# display2.net
KiCad netlist of a schematic drawn in EAGLE
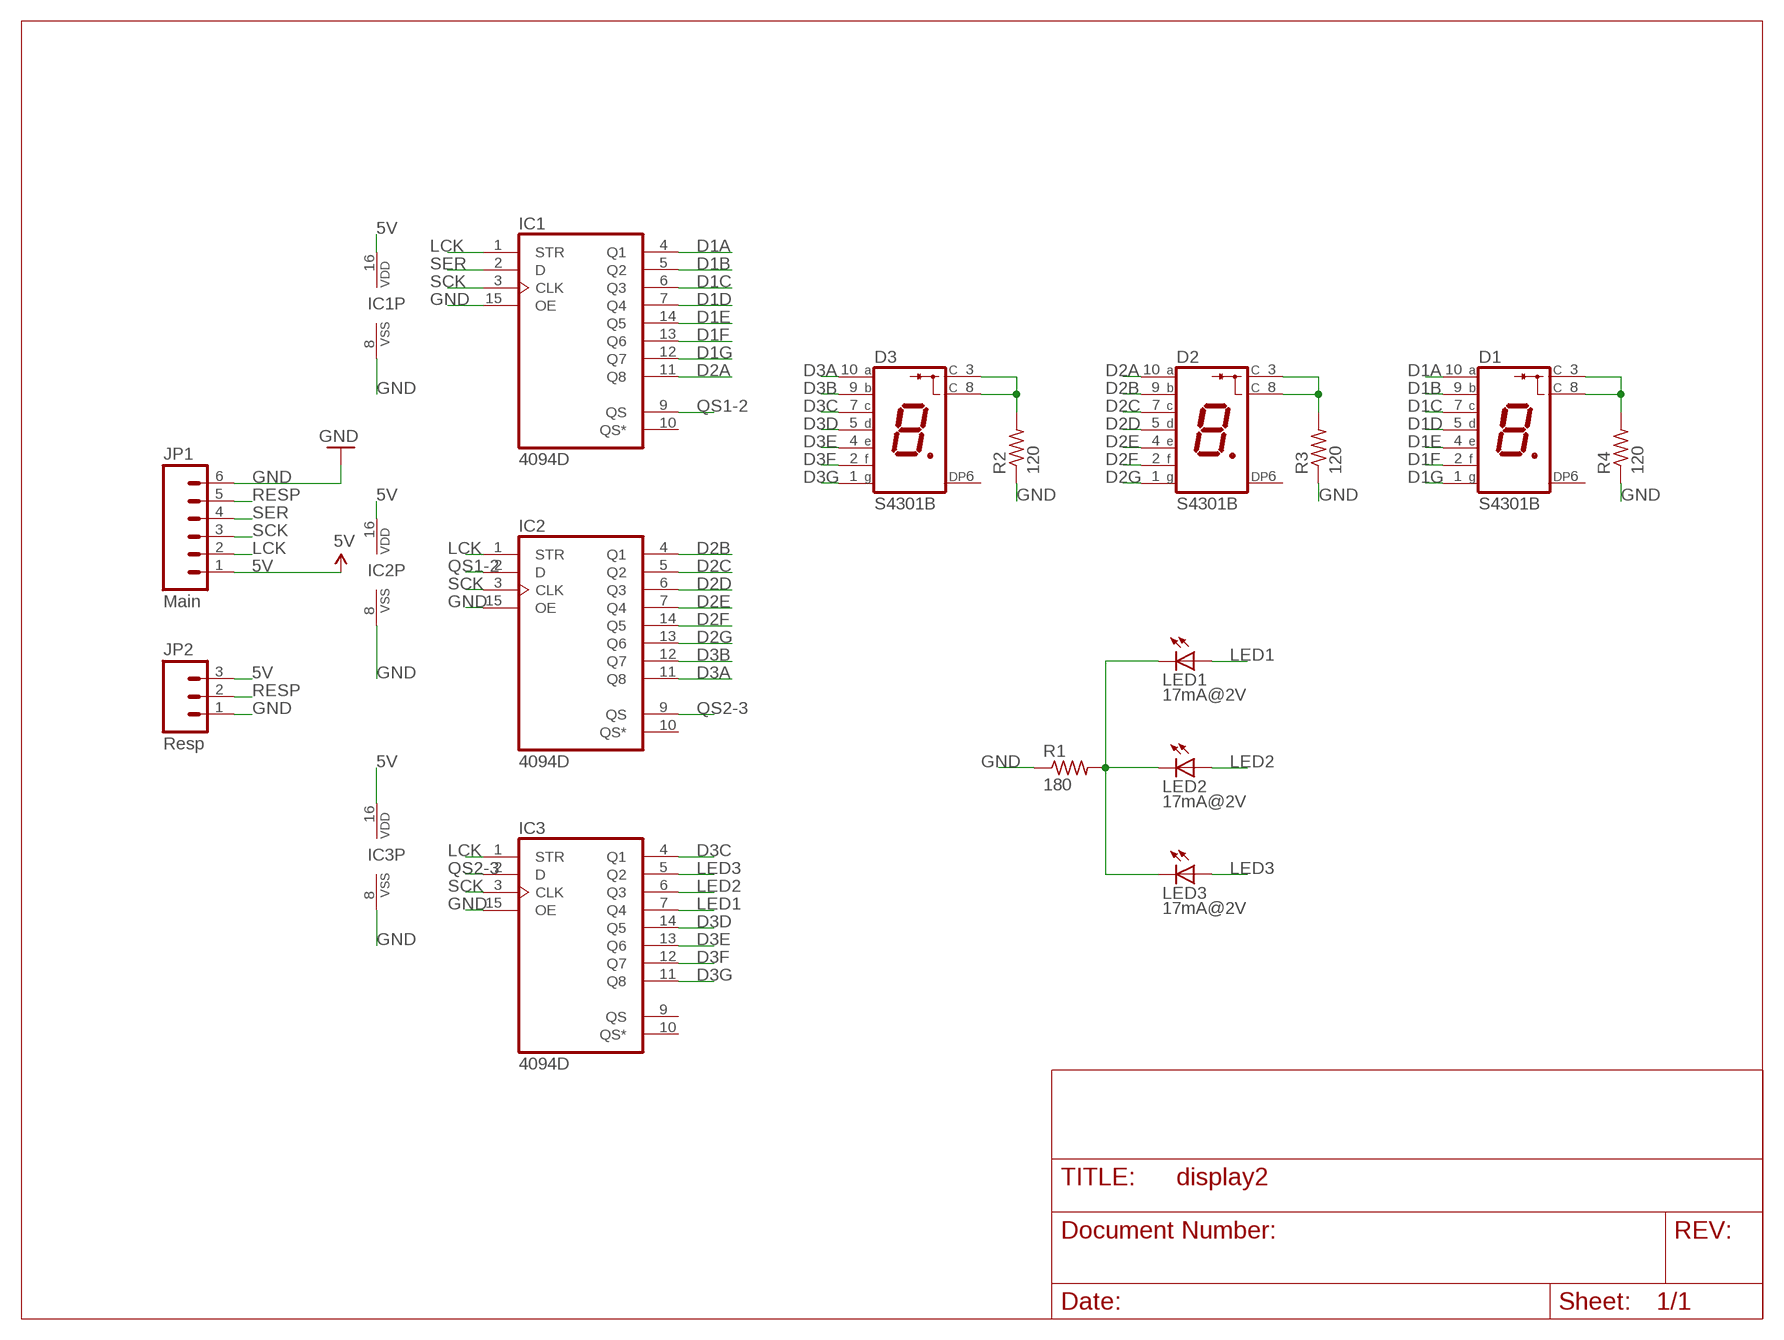
[diagram p0: schematic, sheet 1]

(export (version "E")
  (design (tool "Eeschema 10.0.6"))
  (components
    (comp (ref "D1")
      (value "S4301B")
      (footprint "eagle-import:S4301B")
      (libsource (lib "eagle-import") (part "S4301B"))
    )
    (comp (ref "D2")
      (value "S4301B")
      (footprint "eagle-import:S4301B")
      (libsource (lib "eagle-import") (part "S4301B"))
    )
    (comp (ref "D3")
      (value "S4301B")
      (footprint "eagle-import:S4301B")
      (libsource (lib "eagle-import") (part "S4301B"))
    )
    (comp (ref "IC1")
      (value "4094D")
      (footprint "eagle-import:SO16")
      (libsource (lib "eagle-import") (part "4094D"))
    )
    (comp (ref "IC2")
      (value "4094D")
      (footprint "eagle-import:SO16")
      (libsource (lib "eagle-import") (part "4094D"))
    )
    (comp (ref "IC3")
      (value "4094D")
      (footprint "eagle-import:SO16")
      (libsource (lib "eagle-import") (part "4094D"))
    )
    (comp (ref "JP1")
      (value "Main")
      (footprint "eagle-import:1X06")
      (libsource (lib "eagle-import") (part "M06SIP"))
    )
    (comp (ref "JP2")
      (value "Resp")
      (footprint "eagle-import:1X03")
      (libsource (lib "eagle-import") (part "M03PTH"))
    )
    (comp (ref "LED1")
      (value "17mA@2V")
      (footprint "eagle-import:LED3MM")
      (libsource (lib "eagle-import") (part "LED3MM"))
    )
    (comp (ref "LED2")
      (value "17mA@2V")
      (footprint "eagle-import:LED3MM")
      (libsource (lib "eagle-import") (part "LED3MM"))
    )
    (comp (ref "LED3")
      (value "17mA@2V")
      (footprint "eagle-import:LED3MM")
      (libsource (lib "eagle-import") (part "LED3MM"))
    )
    (comp (ref "R1")
      (value "180")
      (footprint "eagle-import:0204_5")
      (libsource (lib "eagle-import") (part "R-US_0204/5"))
    )
    (comp (ref "R2")
      (value "120")
      (footprint "eagle-import:0204_5")
      (libsource (lib "eagle-import") (part "R-US_0204/5"))
    )
    (comp (ref "R3")
      (value "120")
      (footprint "eagle-import:0204_5")
      (libsource (lib "eagle-import") (part "R-US_0204/5"))
    )
    (comp (ref "R4")
      (value "120")
      (footprint "eagle-import:0204_5")
      (libsource (lib "eagle-import") (part "R-US_0204/5"))
    )
  )
  (nets
    (net (code "1") (name "/D1A") (class "Default")
      (node (ref "D1") (pin "10") (pinfunction "A_10") (pintype "passive"))
      (node (ref "IC1") (pin "4") (pinfunction "Q1_4") (pintype "output"))
    )
    (net (code "2") (name "/D1B") (class "Default")
      (node (ref "D1") (pin "9") (pinfunction "B_9") (pintype "passive"))
      (node (ref "IC1") (pin "5") (pinfunction "Q2_5") (pintype "output"))
    )
    (net (code "3") (name "/D1C") (class "Default")
      (node (ref "D1") (pin "7") (pinfunction "C_7") (pintype "passive"))
      (node (ref "IC1") (pin "6") (pinfunction "Q3_6") (pintype "output"))
    )
    (net (code "4") (name "/D1D") (class "Default")
      (node (ref "D1") (pin "5") (pinfunction "D_5") (pintype "passive"))
      (node (ref "IC1") (pin "7") (pinfunction "Q4_7") (pintype "output"))
    )
    (net (code "5") (name "/D1E") (class "Default")
      (node (ref "D1") (pin "4") (pinfunction "E_4") (pintype "passive"))
      (node (ref "IC1") (pin "14") (pinfunction "Q5_14") (pintype "output"))
    )
    (net (code "6") (name "/D1F") (class "Default")
      (node (ref "D1") (pin "2") (pinfunction "F_2") (pintype "passive"))
      (node (ref "IC1") (pin "13") (pinfunction "Q6_13") (pintype "output"))
    )
    (net (code "7") (name "/D1G") (class "Default")
      (node (ref "D1") (pin "1") (pinfunction "G_1") (pintype "passive"))
      (node (ref "IC1") (pin "12") (pinfunction "Q7_12") (pintype "output"))
    )
    (net (code "8") (name "/D2A") (class "Default")
      (node (ref "D2") (pin "10") (pinfunction "A_10") (pintype "passive"))
      (node (ref "IC1") (pin "11") (pinfunction "Q8_11") (pintype "output"))
    )
    (net (code "9") (name "/D2B") (class "Default")
      (node (ref "D2") (pin "9") (pinfunction "B_9") (pintype "passive"))
      (node (ref "IC2") (pin "4") (pinfunction "Q1_4") (pintype "output"))
    )
    (net (code "10") (name "/D2C") (class "Default")
      (node (ref "D2") (pin "7") (pinfunction "C_7") (pintype "passive"))
      (node (ref "IC2") (pin "5") (pinfunction "Q2_5") (pintype "output"))
    )
    (net (code "11") (name "/D2D") (class "Default")
      (node (ref "D2") (pin "5") (pinfunction "D_5") (pintype "passive"))
      (node (ref "IC2") (pin "6") (pinfunction "Q3_6") (pintype "output"))
    )
    (net (code "12") (name "/D2E") (class "Default")
      (node (ref "D2") (pin "4") (pinfunction "E_4") (pintype "passive"))
      (node (ref "IC2") (pin "7") (pinfunction "Q4_7") (pintype "output"))
    )
    (net (code "13") (name "/D2F") (class "Default")
      (node (ref "D2") (pin "2") (pinfunction "F_2") (pintype "passive"))
      (node (ref "IC2") (pin "14") (pinfunction "Q5_14") (pintype "output"))
    )
    (net (code "14") (name "/D2G") (class "Default")
      (node (ref "D2") (pin "1") (pinfunction "G_1") (pintype "passive"))
      (node (ref "IC2") (pin "13") (pinfunction "Q6_13") (pintype "output"))
    )
    (net (code "15") (name "/D3A") (class "Default")
      (node (ref "D3") (pin "10") (pinfunction "A_10") (pintype "passive"))
      (node (ref "IC2") (pin "11") (pinfunction "Q8_11") (pintype "output"))
    )
    (net (code "16") (name "/D3B") (class "Default")
      (node (ref "D3") (pin "9") (pinfunction "B_9") (pintype "passive"))
      (node (ref "IC2") (pin "12") (pinfunction "Q7_12") (pintype "output"))
    )
    (net (code "17") (name "/D3C") (class "Default")
      (node (ref "D3") (pin "7") (pinfunction "C_7") (pintype "passive"))
      (node (ref "IC3") (pin "4") (pinfunction "Q1_4") (pintype "output"))
    )
    (net (code "18") (name "/D3D") (class "Default")
      (node (ref "D3") (pin "5") (pinfunction "D_5") (pintype "passive"))
      (node (ref "IC3") (pin "14") (pinfunction "Q5_14") (pintype "output"))
    )
    (net (code "19") (name "/D3E") (class "Default")
      (node (ref "D3") (pin "4") (pinfunction "E_4") (pintype "passive"))
      (node (ref "IC3") (pin "13") (pinfunction "Q6_13") (pintype "output"))
    )
    (net (code "20") (name "/D3F") (class "Default")
      (node (ref "D3") (pin "2") (pinfunction "F_2") (pintype "passive"))
      (node (ref "IC3") (pin "12") (pinfunction "Q7_12") (pintype "output"))
    )
    (net (code "21") (name "/D3G") (class "Default")
      (node (ref "D3") (pin "1") (pinfunction "G_1") (pintype "passive"))
      (node (ref "IC3") (pin "11") (pinfunction "Q8_11") (pintype "output"))
    )
    (net (code "22") (name "/LCK") (class "Default")
      (node (ref "IC1") (pin "1") (pinfunction "STR_1") (pintype "input"))
      (node (ref "IC2") (pin "1") (pinfunction "STR_1") (pintype "input"))
      (node (ref "IC3") (pin "1") (pinfunction "STR_1") (pintype "input"))
      (node (ref "JP1") (pin "2") (pinfunction "2_2") (pintype "passive"))
    )
    (net (code "23") (name "/LED1") (class "Default")
      (node (ref "IC3") (pin "7") (pinfunction "Q4_7") (pintype "output"))
      (node (ref "LED1") (pin "A") (pinfunction "A_A") (pintype "passive"))
    )
    (net (code "24") (name "/LED2") (class "Default")
      (node (ref "IC3") (pin "6") (pinfunction "Q3_6") (pintype "output"))
      (node (ref "LED2") (pin "A") (pinfunction "A_A") (pintype "passive"))
    )
    (net (code "25") (name "/LED3") (class "Default")
      (node (ref "IC3") (pin "5") (pinfunction "Q2_5") (pintype "output"))
      (node (ref "LED3") (pin "A") (pinfunction "A_A") (pintype "passive"))
    )
    (net (code "26") (name "/QS1-2") (class "Default")
      (node (ref "IC1") (pin "9") (pinfunction "QS_9") (pintype "output"))
      (node (ref "IC2") (pin "2") (pinfunction "D_2") (pintype "input"))
    )
    (net (code "27") (name "/QS2-3") (class "Default")
      (node (ref "IC2") (pin "9") (pinfunction "QS_9") (pintype "output"))
      (node (ref "IC3") (pin "2") (pinfunction "D_2") (pintype "input"))
    )
    (net (code "28") (name "/RESP") (class "Default")
      (node (ref "JP1") (pin "5") (pinfunction "5_5") (pintype "passive"))
      (node (ref "JP2") (pin "2") (pinfunction "2_2") (pintype "passive"))
    )
    (net (code "29") (name "/SCK") (class "Default")
      (node (ref "IC1") (pin "3") (pinfunction "CLK_3") (pintype "input"))
      (node (ref "IC2") (pin "3") (pinfunction "CLK_3") (pintype "input"))
      (node (ref "IC3") (pin "3") (pinfunction "CLK_3") (pintype "input"))
      (node (ref "JP1") (pin "3") (pinfunction "3_3") (pintype "passive"))
    )
    (net (code "30") (name "/SER") (class "Default")
      (node (ref "IC1") (pin "2") (pinfunction "D_2") (pintype "input"))
      (node (ref "JP1") (pin "4") (pinfunction "4_4") (pintype "passive"))
    )
    (net (code "31") (name "5V") (class "Default")
      (node (ref "IC1") (pin "16") (pinfunction "VDD_16") (pintype "power_in"))
      (node (ref "IC2") (pin "16") (pinfunction "VDD_16") (pintype "power_in"))
      (node (ref "IC3") (pin "16") (pinfunction "VDD_16") (pintype "power_in"))
      (node (ref "JP1") (pin "1") (pinfunction "1_1") (pintype "passive"))
      (node (ref "JP2") (pin "3") (pinfunction "3_3") (pintype "passive"))
    )
    (net (code "32") (name "GND") (class "Default")
      (node (ref "IC1") (pin "15") (pinfunction "OE_15") (pintype "input"))
      (node (ref "IC1") (pin "8") (pinfunction "VSS_8") (pintype "power_in"))
      (node (ref "IC2") (pin "15") (pinfunction "OE_15") (pintype "input"))
      (node (ref "IC2") (pin "8") (pinfunction "VSS_8") (pintype "power_in"))
      (node (ref "IC3") (pin "15") (pinfunction "OE_15") (pintype "input"))
      (node (ref "IC3") (pin "8") (pinfunction "VSS_8") (pintype "power_in"))
      (node (ref "JP1") (pin "6") (pinfunction "6_6") (pintype "passive"))
      (node (ref "JP2") (pin "1") (pinfunction "1_1") (pintype "passive"))
      (node (ref "R1") (pin "1") (pinfunction "1_1") (pintype "passive"))
      (node (ref "R2") (pin "1") (pinfunction "1_1") (pintype "passive"))
      (node (ref "R3") (pin "1") (pinfunction "1_1") (pintype "passive"))
      (node (ref "R4") (pin "1") (pinfunction "1_1") (pintype "passive"))
    )
    (net (code "33") (name "Net-(D1-C-Pad3)") (class "Default")
      (node (ref "D1") (pin "3") (pinfunction "C_3") (pintype "passive"))
      (node (ref "D1") (pin "8") (pinfunction "C_8") (pintype "passive"))
      (node (ref "R4") (pin "2") (pinfunction "2_2") (pintype "passive"))
    )
    (net (code "34") (name "Net-(D2-C-Pad3)") (class "Default")
      (node (ref "D2") (pin "3") (pinfunction "C_3") (pintype "passive"))
      (node (ref "D2") (pin "8") (pinfunction "C_8") (pintype "passive"))
      (node (ref "R3") (pin "2") (pinfunction "2_2") (pintype "passive"))
    )
    (net (code "35") (name "Net-(D3-C-Pad3)") (class "Default")
      (node (ref "D3") (pin "3") (pinfunction "C_3") (pintype "passive"))
      (node (ref "D3") (pin "8") (pinfunction "C_8") (pintype "passive"))
      (node (ref "R2") (pin "2") (pinfunction "2_2") (pintype "passive"))
    )
    (net (code "36") (name "Net-(LED1-C)") (class "Default")
      (node (ref "LED1") (pin "K") (pinfunction "C_K") (pintype "passive"))
      (node (ref "LED2") (pin "K") (pinfunction "C_K") (pintype "passive"))
      (node (ref "LED3") (pin "K") (pinfunction "C_K") (pintype "passive"))
      (node (ref "R1") (pin "2") (pinfunction "2_2") (pintype "passive"))
    )
    (net (code "37") (name "unconnected-(D1-DP-Pad6)") (class "Default")
      (node (ref "D1") (pin "6") (pinfunction "DP_6") (pintype "passive"))
    )
    (net (code "38") (name "unconnected-(D2-DP-Pad6)") (class "Default")
      (node (ref "D2") (pin "6") (pinfunction "DP_6") (pintype "passive"))
    )
    (net (code "39") (name "unconnected-(D3-DP-Pad6)") (class "Default")
      (node (ref "D3") (pin "6") (pinfunction "DP_6") (pintype "passive"))
    )
    (net (code "40") (name "unconnected-(IC1A-QS*-Pad10)") (class "Default")
      (node (ref "IC1") (pin "10") (pinfunction "QS*_10") (pintype "output"))
    )
    (net (code "41") (name "unconnected-(IC2A-QS*-Pad10)") (class "Default")
      (node (ref "IC2") (pin "10") (pinfunction "QS*_10") (pintype "output"))
    )
    (net (code "42") (name "unconnected-(IC3A-QS*-Pad10)") (class "Default")
      (node (ref "IC3") (pin "10") (pinfunction "QS*_10") (pintype "output"))
    )
    (net (code "43") (name "unconnected-(IC3A-QS-Pad9)") (class "Default")
      (node (ref "IC3") (pin "9") (pinfunction "QS_9") (pintype "output"))
    )
  )
)
